# dpad.net
KiCad netlist of a schematic drawn in EAGLE
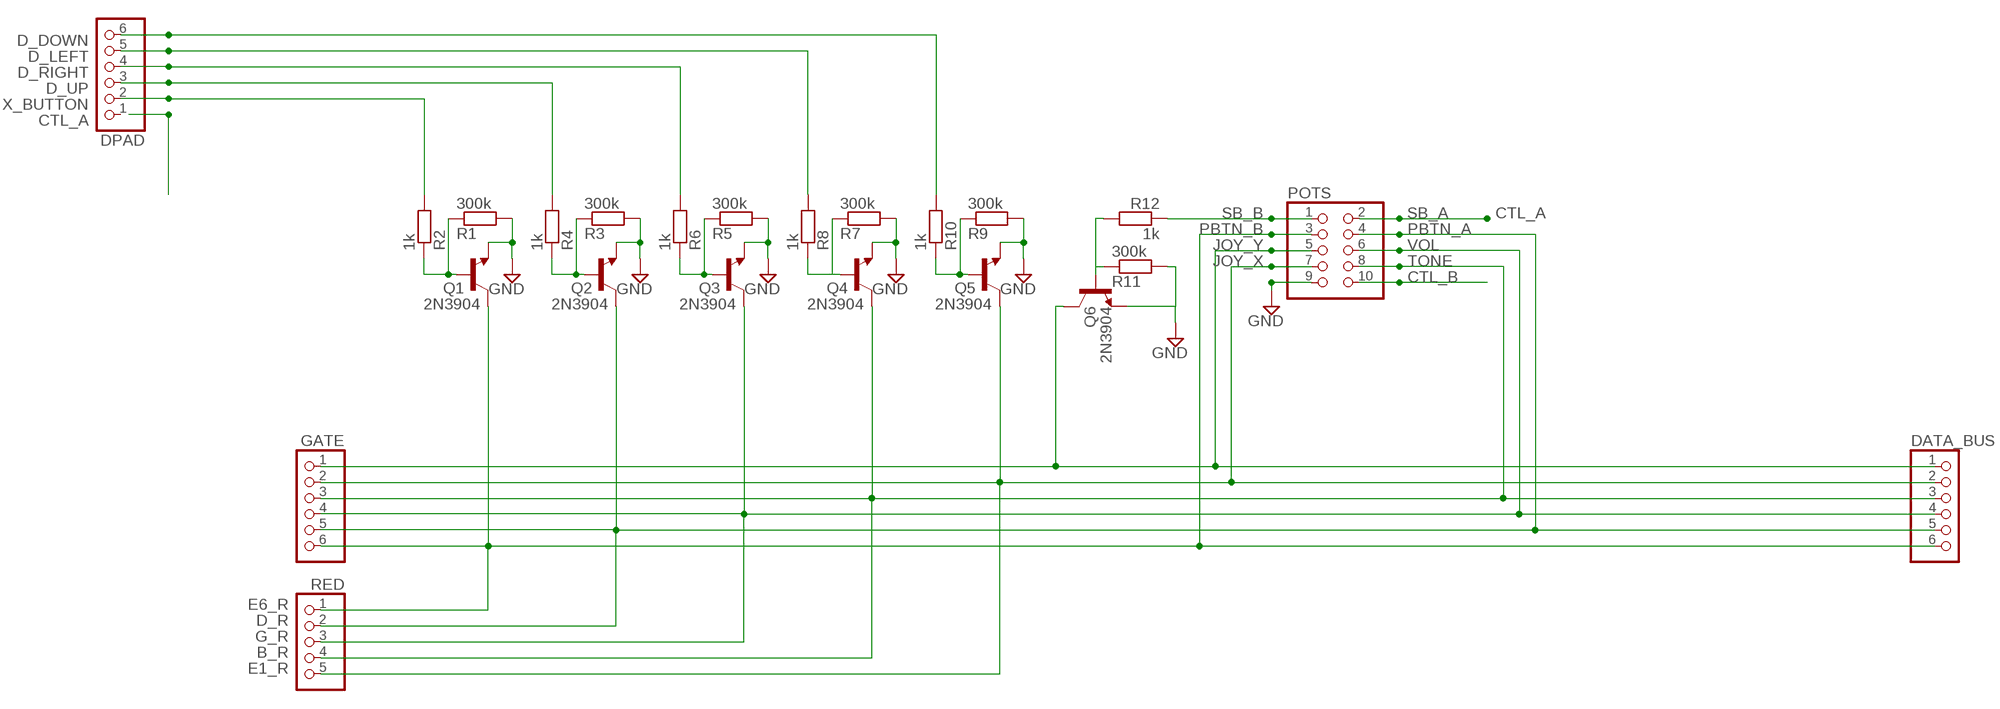
[diagram p0: schematic, sheet 1]

(export (version "E")
  (design (tool "Eeschema 10.0.6"))
  (components
    (comp (ref "DATA_BUS")
      (value "PINHD-1X6")
      (footprint "eagle-import:1X06")
      (libsource (lib "eagle-import") (part "PINHD-1X6"))
    )
    (comp (ref "DPAD")
      (value "PINHD-1X6")
      (footprint "eagle-import:1X06")
      (libsource (lib "eagle-import") (part "PINHD-1X6"))
    )
    (comp (ref "GATE")
      (value "PINHD-1X6")
      (footprint "eagle-import:1X06")
      (libsource (lib "eagle-import") (part "PINHD-1X6"))
    )
    (comp (ref "POTS")
      (value "PINHD-2X5")
      (footprint "eagle-import:2X05")
      (libsource (lib "eagle-import") (part "PINHD-2X5"))
    )
    (comp (ref "Q1")
      (value "2N3904")
      (footprint "eagle-import:TO92-")
      (libsource (lib "eagle-import") (part "2N3904"))
    )
    (comp (ref "Q2")
      (value "2N3904")
      (footprint "eagle-import:TO92-")
      (libsource (lib "eagle-import") (part "2N3904"))
    )
    (comp (ref "Q3")
      (value "2N3904")
      (footprint "eagle-import:TO92-")
      (libsource (lib "eagle-import") (part "2N3904"))
    )
    (comp (ref "Q4")
      (value "2N3904")
      (footprint "eagle-import:TO92-")
      (libsource (lib "eagle-import") (part "2N3904"))
    )
    (comp (ref "Q5")
      (value "2N3904")
      (footprint "eagle-import:TO92-")
      (libsource (lib "eagle-import") (part "2N3904"))
    )
    (comp (ref "Q6")
      (value "2N3904")
      (footprint "eagle-import:TO92-")
      (libsource (lib "eagle-import") (part "2N3904"))
    )
    (comp (ref "R1")
      (value "300k")
      (footprint "eagle-import:R0207_1V")
      (libsource (lib "eagle-import") (part "6MM-EU1"))
    )
    (comp (ref "R2")
      (value "1k")
      (footprint "eagle-import:R0207_1V")
      (libsource (lib "eagle-import") (part "6MM-EU1"))
    )
    (comp (ref "R3")
      (value "300k")
      (footprint "eagle-import:R0207_1V")
      (libsource (lib "eagle-import") (part "6MM-EU1"))
    )
    (comp (ref "R4")
      (value "1k")
      (footprint "eagle-import:R0207_1V")
      (libsource (lib "eagle-import") (part "6MM-EU1"))
    )
    (comp (ref "R5")
      (value "300k")
      (footprint "eagle-import:R0207_1V")
      (libsource (lib "eagle-import") (part "6MM-EU1"))
    )
    (comp (ref "R6")
      (value "1k")
      (footprint "eagle-import:R0207_1V")
      (libsource (lib "eagle-import") (part "6MM-EU1"))
    )
    (comp (ref "R7")
      (value "300k")
      (footprint "eagle-import:R0207_1V")
      (libsource (lib "eagle-import") (part "6MM-EU1"))
    )
    (comp (ref "R8")
      (value "1k")
      (footprint "eagle-import:R0207_1V")
      (libsource (lib "eagle-import") (part "6MM-EU1"))
    )
    (comp (ref "R9")
      (value "300k")
      (footprint "eagle-import:R0207_1V")
      (libsource (lib "eagle-import") (part "6MM-EU1"))
    )
    (comp (ref "R10")
      (value "1k")
      (footprint "eagle-import:R0207_1V")
      (libsource (lib "eagle-import") (part "6MM-EU1"))
    )
    (comp (ref "R11")
      (value "300k")
      (footprint "eagle-import:R0207_1V")
      (libsource (lib "eagle-import") (part "6MM-EU1"))
    )
    (comp (ref "R12")
      (value "1k")
      (footprint "eagle-import:R0207_1V")
      (libsource (lib "eagle-import") (part "6MM-EU1"))
    )
    (comp (ref "RED")
      (value "PINHD-1X5")
      (footprint "eagle-import:1X05")
      (libsource (lib "eagle-import") (part "PINHD-1X5"))
    )
  )
  (nets
    (net (code "1") (name "/CTL_A") (class "Default")
      (node (ref "POTS") (pin "2") (pinfunction "2_2") (pintype "passive"))
    )
    (net (code "2") (name "/D_DOWN") (class "Default")
      (node (ref "DPAD") (pin "6") (pinfunction "6_6") (pintype "passive"))
      (node (ref "R10") (pin "2") (pinfunction "2_2") (pintype "passive"))
    )
    (net (code "3") (name "/D_LEFT") (class "Default")
      (node (ref "DPAD") (pin "5") (pinfunction "5_5") (pintype "passive"))
      (node (ref "R8") (pin "2") (pinfunction "2_2") (pintype "passive"))
    )
    (net (code "4") (name "/D_RIGHT") (class "Default")
      (node (ref "DPAD") (pin "4") (pinfunction "4_4") (pintype "passive"))
      (node (ref "R6") (pin "2") (pinfunction "2_2") (pintype "passive"))
    )
    (net (code "5") (name "/D_UP") (class "Default")
      (node (ref "DPAD") (pin "3") (pinfunction "3_3") (pintype "passive"))
      (node (ref "R4") (pin "2") (pinfunction "2_2") (pintype "passive"))
    )
    (net (code "6") (name "/X_BUTTON") (class "Default")
      (node (ref "DPAD") (pin "2") (pinfunction "2_2") (pintype "passive"))
      (node (ref "R2") (pin "2") (pinfunction "2_2") (pintype "passive"))
    )
    (net (code "7") (name "GND") (class "Default")
      (node (ref "POTS") (pin "9") (pinfunction "9_9") (pintype "passive"))
      (node (ref "Q1") (pin "3") (pinfunction "E_3") (pintype "passive"))
      (node (ref "Q2") (pin "3") (pinfunction "E_3") (pintype "passive"))
      (node (ref "Q3") (pin "3") (pinfunction "E_3") (pintype "passive"))
      (node (ref "Q4") (pin "3") (pinfunction "E_3") (pintype "passive"))
      (node (ref "Q5") (pin "3") (pinfunction "E_3") (pintype "passive"))
      (node (ref "Q6") (pin "3") (pinfunction "E_3") (pintype "passive"))
      (node (ref "R1") (pin "2") (pinfunction "2_2") (pintype "passive"))
      (node (ref "R11") (pin "2") (pinfunction "2_2") (pintype "passive"))
      (node (ref "R3") (pin "2") (pinfunction "2_2") (pintype "passive"))
      (node (ref "R5") (pin "2") (pinfunction "2_2") (pintype "passive"))
      (node (ref "R7") (pin "2") (pinfunction "2_2") (pintype "passive"))
      (node (ref "R9") (pin "2") (pinfunction "2_2") (pintype "passive"))
    )
    (net (code "8") (name "Net-(POTS-Pad1)") (class "Default")
      (node (ref "POTS") (pin "1") (pinfunction "1_1") (pintype "passive"))
      (node (ref "R12") (pin "1") (pinfunction "1_1") (pintype "passive"))
    )
    (net (code "9") (name "Net-(Q1-B)") (class "Default")
      (node (ref "Q1") (pin "2") (pinfunction "B_2") (pintype "passive"))
      (node (ref "R1") (pin "1") (pinfunction "1_1") (pintype "passive"))
      (node (ref "R2") (pin "1") (pinfunction "1_1") (pintype "passive"))
    )
    (net (code "10") (name "Net-(Q1-C)") (class "Default")
      (node (ref "DATA_BUS") (pin "6") (pinfunction "6_6") (pintype "passive"))
      (node (ref "GATE") (pin "6") (pinfunction "6_6") (pintype "passive"))
      (node (ref "POTS") (pin "3") (pinfunction "3_3") (pintype "passive"))
      (node (ref "Q1") (pin "1") (pinfunction "C_1") (pintype "passive"))
      (node (ref "RED") (pin "1") (pinfunction "1_1") (pintype "passive"))
    )
    (net (code "11") (name "Net-(Q2-B)") (class "Default")
      (node (ref "Q2") (pin "2") (pinfunction "B_2") (pintype "passive"))
      (node (ref "R3") (pin "1") (pinfunction "1_1") (pintype "passive"))
      (node (ref "R4") (pin "1") (pinfunction "1_1") (pintype "passive"))
    )
    (net (code "12") (name "Net-(Q2-C)") (class "Default")
      (node (ref "DATA_BUS") (pin "5") (pinfunction "5_5") (pintype "passive"))
      (node (ref "GATE") (pin "5") (pinfunction "5_5") (pintype "passive"))
      (node (ref "POTS") (pin "4") (pinfunction "4_4") (pintype "passive"))
      (node (ref "Q2") (pin "1") (pinfunction "C_1") (pintype "passive"))
      (node (ref "RED") (pin "2") (pinfunction "2_2") (pintype "passive"))
    )
    (net (code "13") (name "Net-(Q3-B)") (class "Default")
      (node (ref "Q3") (pin "2") (pinfunction "B_2") (pintype "passive"))
      (node (ref "R5") (pin "1") (pinfunction "1_1") (pintype "passive"))
      (node (ref "R6") (pin "1") (pinfunction "1_1") (pintype "passive"))
    )
    (net (code "14") (name "Net-(Q3-C)") (class "Default")
      (node (ref "DATA_BUS") (pin "4") (pinfunction "4_4") (pintype "passive"))
      (node (ref "GATE") (pin "4") (pinfunction "4_4") (pintype "passive"))
      (node (ref "POTS") (pin "6") (pinfunction "6_6") (pintype "passive"))
      (node (ref "Q3") (pin "1") (pinfunction "C_1") (pintype "passive"))
      (node (ref "RED") (pin "3") (pinfunction "3_3") (pintype "passive"))
    )
    (net (code "15") (name "Net-(Q4-B)") (class "Default")
      (node (ref "Q4") (pin "2") (pinfunction "B_2") (pintype "passive"))
      (node (ref "R7") (pin "1") (pinfunction "1_1") (pintype "passive"))
      (node (ref "R8") (pin "1") (pinfunction "1_1") (pintype "passive"))
    )
    (net (code "16") (name "Net-(Q4-C)") (class "Default")
      (node (ref "DATA_BUS") (pin "3") (pinfunction "3_3") (pintype "passive"))
      (node (ref "GATE") (pin "3") (pinfunction "3_3") (pintype "passive"))
      (node (ref "POTS") (pin "8") (pinfunction "8_8") (pintype "passive"))
      (node (ref "Q4") (pin "1") (pinfunction "C_1") (pintype "passive"))
      (node (ref "RED") (pin "4") (pinfunction "4_4") (pintype "passive"))
    )
    (net (code "17") (name "Net-(Q5-B)") (class "Default")
      (node (ref "Q5") (pin "2") (pinfunction "B_2") (pintype "passive"))
      (node (ref "R10") (pin "1") (pinfunction "1_1") (pintype "passive"))
      (node (ref "R9") (pin "1") (pinfunction "1_1") (pintype "passive"))
    )
    (net (code "18") (name "Net-(Q5-C)") (class "Default")
      (node (ref "DATA_BUS") (pin "2") (pinfunction "2_2") (pintype "passive"))
      (node (ref "GATE") (pin "2") (pinfunction "2_2") (pintype "passive"))
      (node (ref "POTS") (pin "7") (pinfunction "7_7") (pintype "passive"))
      (node (ref "Q5") (pin "1") (pinfunction "C_1") (pintype "passive"))
      (node (ref "RED") (pin "5") (pinfunction "5_5") (pintype "passive"))
    )
    (net (code "19") (name "Net-(Q6-B)") (class "Default")
      (node (ref "Q6") (pin "2") (pinfunction "B_2") (pintype "passive"))
      (node (ref "R11") (pin "1") (pinfunction "1_1") (pintype "passive"))
      (node (ref "R12") (pin "2") (pinfunction "2_2") (pintype "passive"))
    )
    (net (code "20") (name "Net-(Q6-C)") (class "Default")
      (node (ref "DATA_BUS") (pin "1") (pinfunction "1_1") (pintype "passive"))
      (node (ref "GATE") (pin "1") (pinfunction "1_1") (pintype "passive"))
      (node (ref "POTS") (pin "5") (pinfunction "5_5") (pintype "passive"))
      (node (ref "Q6") (pin "1") (pinfunction "C_1") (pintype "passive"))
    )
    (net (code "21") (name "unconnected-(DPAD-Pad1)") (class "Default")
      (node (ref "DPAD") (pin "1") (pinfunction "1_1") (pintype "passive"))
    )
    (net (code "22") (name "unconnected-(POTS-Pad10)") (class "Default")
      (node (ref "POTS") (pin "10") (pinfunction "10_10") (pintype "passive"))
    )
  )
)
